# Contactor_Switching.net
KiCad netlist of a schematic drawn in Altium Designer
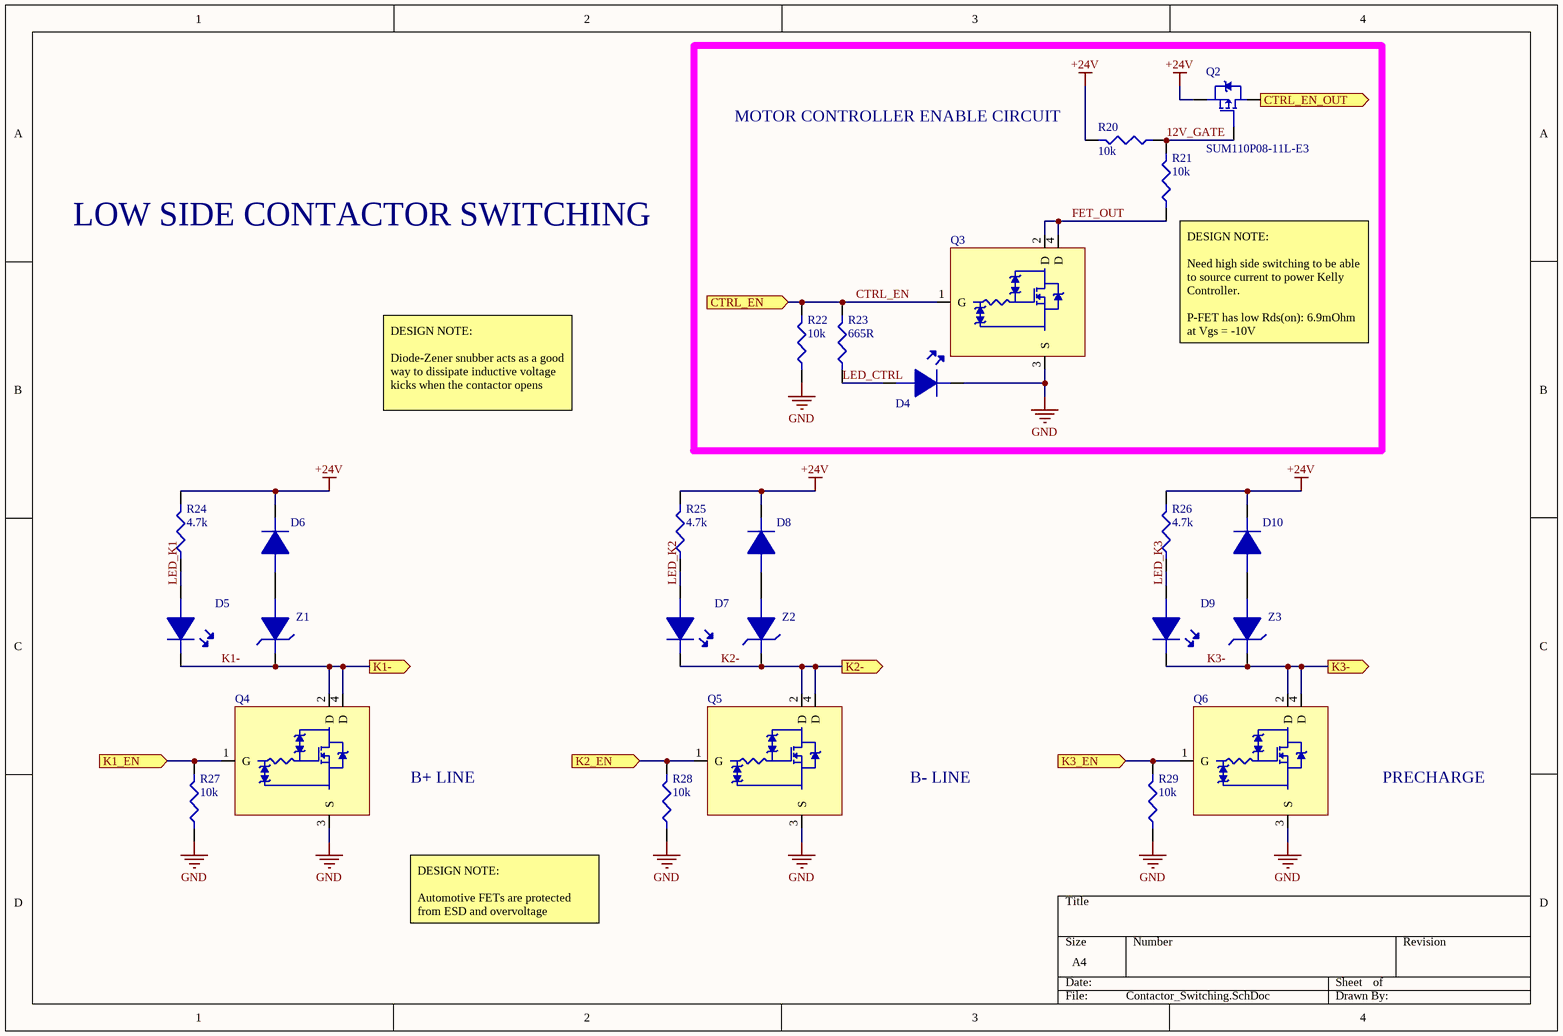
[diagram p0: Contactor_Switching.SchDoc]

(export (version "E")
  (design (tool "Eeschema 10.0.6"))
  (components
    (comp (ref "D4")
      (value "LTST-C191TBKT-5A")
      (footprint "LED_0603")
      (description "LED BLUE CLEAR 0603 SMD")
      (fields (field (name "MANUFACTURER") "Vishay Lite-On") (field (name "VOLTAGE") "29V"))
      (libsource (lib "PHANTOM_LIBRARY") (part "LTST-C191TBKT-5A"))
    )
    (comp (ref "D5")
      (value "LTST-C191TBKT-5A")
      (footprint "LED_0603")
      (description "LED BLUE CLEAR 0603 SMD")
      (fields (field (name "MANUFACTURER") "Vishay Lite-On") (field (name "VOLTAGE") "29V"))
      (libsource (lib "PHANTOM_LIBRARY") (part "LTST-C191TBKT-5A"))
    )
    (comp (ref "D6")
      (value "S3BB-TP")
      (footprint "DO-214AA_Diode")
      (description "DIODE GEN PURP 100V 3A DO214AA")
      (fields (field (name "MANUFACTURER") "MCC"))
      (libsource (lib "PHANTOM_LIBRARY") (part "S3BB-TP"))
    )
    (comp (ref "D7")
      (value "LTST-C191TBKT-5A")
      (footprint "LED_0603")
      (description "LED BLUE CLEAR 0603 SMD")
      (fields (field (name "MANUFACTURER") "Vishay Lite-On") (field (name "VOLTAGE") "29V"))
      (libsource (lib "PHANTOM_LIBRARY") (part "LTST-C191TBKT-5A"))
    )
    (comp (ref "D8")
      (value "S3BB-TP")
      (footprint "DO-214AA_Diode")
      (description "DIODE GEN PURP 100V 3A DO214AA")
      (fields (field (name "MANUFACTURER") "MCC"))
      (libsource (lib "PHANTOM_LIBRARY") (part "S3BB-TP"))
    )
    (comp (ref "D9")
      (value "LTST-C191TBKT-5A")
      (footprint "LED_0603")
      (description "LED BLUE CLEAR 0603 SMD")
      (fields (field (name "MANUFACTURER") "Vishay Lite-On") (field (name "VOLTAGE") "29V"))
      (libsource (lib "PHANTOM_LIBRARY") (part "LTST-C191TBKT-5A"))
    )
    (comp (ref "D10")
      (value "S3BB-TP")
      (footprint "DO-214AA_Diode")
      (description "DIODE GEN PURP 100V 3A DO214AA")
      (fields (field (name "MANUFACTURER") "MCC"))
      (libsource (lib "PHANTOM_LIBRARY") (part "S3BB-TP"))
    )
    (comp (ref "Q2")
      (value "SUM110P08-11L-E3")
      (footprint "D2PAK_FETs")
      (description "Trans MOSFET P-CH 80V 23.5A 3-Pin(2+Tab) TO-263")
      (fields (field (name "MANUFACTURER") "Vishay"))
      (libsource (lib "PHANTOM_LIBRARY") (part "SUM110P08-11L-E3"))
    )
    (comp (ref "Q3")
      (value "NCV8406ASTT1G")
      (footprint "SOT-223_NFET")
      (description "Self-Protected Low Side Driver Automotive 4-Pin(3+Tab) SOT-223 T/R")
      (fields (field (name "MANUFACTURER") "ON Semiconductor"))
      (libsource (lib "PHANTOM_LIBRARY") (part "NCV8406ASTT1G"))
    )
    (comp (ref "Q4")
      (value "NCV8406ASTT1G")
      (footprint "SOT-223_NFET")
      (description "Self-Protected Low Side Driver Automotive 4-Pin(3+Tab) SOT-223 T/R")
      (fields (field (name "MANUFACTURER") "ON Semiconductor"))
      (libsource (lib "PHANTOM_LIBRARY") (part "NCV8406ASTT1G"))
    )
    (comp (ref "Q5")
      (value "NCV8406ASTT1G")
      (footprint "SOT-223_NFET")
      (description "Self-Protected Low Side Driver Automotive 4-Pin(3+Tab) SOT-223 T/R")
      (fields (field (name "MANUFACTURER") "ON Semiconductor"))
      (libsource (lib "PHANTOM_LIBRARY") (part "NCV8406ASTT1G"))
    )
    (comp (ref "Q6")
      (value "NCV8406ASTT1G")
      (footprint "SOT-223_NFET")
      (description "Self-Protected Low Side Driver Automotive 4-Pin(3+Tab) SOT-223 T/R")
      (fields (field (name "MANUFACTURER") "ON Semiconductor"))
      (libsource (lib "PHANTOM_LIBRARY") (part "NCV8406ASTT1G"))
    )
    (comp (ref "R20")
      (value "10k")
      (footprint "R0805")
      (description "RES SMD 10K OHM 1% 1/8W 0805")
      (fields
        (field (name "MANUFACTURER") "Yageo Phycomp")
        (field (name "MANUFACTURER PART NUMBER") "RC0805FR-071KL")
      )
      (libsource (lib "PHANTOM_LIBRARY") (part "RC0805FR-071KL"))
    )
    (comp (ref "R21")
      (value "10k")
      (footprint "R0805")
      (description "RES SMD 10K OHM 1% 1/8W 0805")
      (fields
        (field (name "MANUFACTURER") "Yageo Phycomp")
        (field (name "MANUFACTURER PART NUMBER") "RC0805FR-071KL")
      )
      (libsource (lib "PHANTOM_LIBRARY") (part "RC0805FR-071KL"))
    )
    (comp (ref "R22")
      (value "10k")
      (footprint "R0805")
      (description "RES SMD 10K OHM 1% 1/8W 0805")
      (fields
        (field (name "MANUFACTURER") "Yageo Phycomp")
        (field (name "MANUFACTURER PART NUMBER") "RC0805FR-071KL")
      )
      (libsource (lib "PHANTOM_LIBRARY") (part "RC0805FR-071KL"))
    )
    (comp (ref "R23")
      (value "665R")
      (footprint "R0805")
      (description "RES SMD 665 OHM 1% 1/8W 0805")
      (fields
        (field (name "MANUFACTURER") "Yageo")
        (field (name "MANUFACTURER PART NUMBER") "RC0805FR-07665RL")
      )
      (libsource (lib "PHANTOM_LIBRARY") (part "RC0805FR-07665RL"))
    )
    (comp (ref "R24")
      (value "4.7k")
      (footprint "R0805")
      (description "RES SMD 4.7K OHM 1% 1/8W 0805")
      (fields
        (field (name "MANUFACTURER") "Yageo")
        (field (name "MANUFACTURER PART NUMBER") "RC0805FR-074K7L")
      )
      (libsource (lib "PHANTOM_LIBRARY") (part "RC0805FR-074K7L"))
    )
    (comp (ref "R25")
      (value "4.7k")
      (footprint "R0805")
      (description "RES SMD 4.7K OHM 1% 1/8W 0805")
      (fields
        (field (name "MANUFACTURER") "Yageo")
        (field (name "MANUFACTURER PART NUMBER") "RC0805FR-074K7L")
      )
      (libsource (lib "PHANTOM_LIBRARY") (part "RC0805FR-074K7L"))
    )
    (comp (ref "R26")
      (value "4.7k")
      (footprint "R0805")
      (description "RES SMD 4.7K OHM 1% 1/8W 0805")
      (fields
        (field (name "MANUFACTURER") "Yageo")
        (field (name "MANUFACTURER PART NUMBER") "RC0805FR-074K7L")
      )
      (libsource (lib "PHANTOM_LIBRARY") (part "RC0805FR-074K7L"))
    )
    (comp (ref "R27")
      (value "10k")
      (footprint "R0805")
      (description "RES SMD 10K OHM 1% 1/8W 0805")
      (fields
        (field (name "MANUFACTURER") "Yageo Phycomp")
        (field (name "MANUFACTURER PART NUMBER") "RC0805FR-071KL")
      )
      (libsource (lib "PHANTOM_LIBRARY") (part "RC0805FR-071KL"))
    )
    (comp (ref "R28")
      (value "10k")
      (footprint "R0805")
      (description "RES SMD 10K OHM 1% 1/8W 0805")
      (fields
        (field (name "MANUFACTURER") "Yageo Phycomp")
        (field (name "MANUFACTURER PART NUMBER") "RC0805FR-071KL")
      )
      (libsource (lib "PHANTOM_LIBRARY") (part "RC0805FR-071KL"))
    )
    (comp (ref "R29")
      (value "10k")
      (footprint "R0805")
      (description "RES SMD 10K OHM 1% 1/8W 0805")
      (fields
        (field (name "MANUFACTURER") "Yageo Phycomp")
        (field (name "MANUFACTURER PART NUMBER") "RC0805FR-071KL")
      )
      (libsource (lib "PHANTOM_LIBRARY") (part "RC0805FR-071KL"))
    )
    (comp (ref "Z1")
      (value "12V")
      (footprint "DO-214AA_Diode")
      (description "DIODE ZENER 12V 5W DO214AA")
      (fields (field (name "MANUFACTURER") "MCC") (field (name "MANUFACTURER PART NUMBER") "SMBJ5349B-TP"))
      (libsource (lib "PHANTOM_LIBRARY") (part "SMBJ5349B-TP"))
    )
    (comp (ref "Z2")
      (value "12V")
      (footprint "DO-214AA_Diode")
      (description "DIODE ZENER 12V 5W DO214AA")
      (fields (field (name "MANUFACTURER") "MCC") (field (name "MANUFACTURER PART NUMBER") "SMBJ5349B-TP"))
      (libsource (lib "PHANTOM_LIBRARY") (part "SMBJ5349B-TP"))
    )
    (comp (ref "Z3")
      (value "12V")
      (footprint "DO-214AA_Diode")
      (description "DIODE ZENER 12V 5W DO214AA")
      (fields (field (name "MANUFACTURER") "MCC") (field (name "MANUFACTURER PART NUMBER") "SMBJ5349B-TP"))
      (libsource (lib "PHANTOM_LIBRARY") (part "SMBJ5349B-TP"))
    )
  )
  (nets
    (net (code "1") (name "+24V") (class "Default")
      (node (ref "D10") (pin "2") (pinfunction "2_2") (pintype "passive"))
      (node (ref "D6") (pin "2") (pinfunction "2_2") (pintype "passive"))
      (node (ref "D8") (pin "2") (pinfunction "2_2") (pintype "passive"))
      (node (ref "Q2") (pin "4") (pinfunction "4_4") (pintype "passive"))
      (node (ref "R20") (pin "2") (pinfunction "2_2") (pintype "passive"))
      (node (ref "R24") (pin "2") (pinfunction "2_2") (pintype "passive"))
      (node (ref "R25") (pin "2") (pinfunction "2_2") (pintype "passive"))
      (node (ref "R26") (pin "2") (pinfunction "2_2") (pintype "passive"))
    )
    (net (code "2") (name "/12V_GATE") (class "Default")
      (node (ref "Q2") (pin "1") (pinfunction "1_1") (pintype "passive"))
      (node (ref "R20") (pin "1") (pinfunction "1_1") (pintype "passive"))
      (node (ref "R21") (pin "2") (pinfunction "2_2") (pintype "passive"))
    )
    (net (code "3") (name "/CTRL_EN") (class "Default")
      (node (ref "Q3") (pin "1") (pinfunction "G_1") (pintype "passive"))
      (node (ref "R22") (pin "2") (pinfunction "2_2") (pintype "passive"))
      (node (ref "R23") (pin "2") (pinfunction "2_2") (pintype "passive"))
    )
    (net (code "4") (name "/CTRL_EN_OUT") (class "Default")
      (node (ref "Q2") (pin "3") (pinfunction "3_3") (pintype "passive"))
    )
    (net (code "5") (name "/FET_OUT") (class "Default")
      (node (ref "Q3") (pin "2") (pinfunction "D_2") (pintype "passive"))
      (node (ref "Q3") (pin "4") (pinfunction "D_4") (pintype "passive"))
      (node (ref "R21") (pin "1") (pinfunction "1_1") (pintype "passive"))
    )
    (net (code "6") (name "/K1-") (class "Default")
      (node (ref "D5") (pin "2") (pinfunction "2_2") (pintype "passive"))
      (node (ref "Q4") (pin "2") (pinfunction "D_2") (pintype "passive"))
      (node (ref "Q4") (pin "4") (pinfunction "D_4") (pintype "passive"))
      (node (ref "Z1") (pin "2") (pinfunction "2_2") (pintype "passive"))
    )
    (net (code "7") (name "/K1_EN") (class "Default")
      (node (ref "Q4") (pin "1") (pinfunction "G_1") (pintype "passive"))
      (node (ref "R27") (pin "2") (pinfunction "2_2") (pintype "passive"))
    )
    (net (code "8") (name "/K2-") (class "Default")
      (node (ref "D7") (pin "2") (pinfunction "2_2") (pintype "passive"))
      (node (ref "Q5") (pin "2") (pinfunction "D_2") (pintype "passive"))
      (node (ref "Q5") (pin "4") (pinfunction "D_4") (pintype "passive"))
      (node (ref "Z2") (pin "2") (pinfunction "2_2") (pintype "passive"))
    )
    (net (code "9") (name "/K2_EN") (class "Default")
      (node (ref "Q5") (pin "1") (pinfunction "G_1") (pintype "passive"))
      (node (ref "R28") (pin "2") (pinfunction "2_2") (pintype "passive"))
    )
    (net (code "10") (name "/K3-") (class "Default")
      (node (ref "D9") (pin "2") (pinfunction "2_2") (pintype "passive"))
      (node (ref "Q6") (pin "2") (pinfunction "D_2") (pintype "passive"))
      (node (ref "Q6") (pin "4") (pinfunction "D_4") (pintype "passive"))
      (node (ref "Z3") (pin "2") (pinfunction "2_2") (pintype "passive"))
    )
    (net (code "11") (name "/K3_EN") (class "Default")
      (node (ref "Q6") (pin "1") (pinfunction "G_1") (pintype "passive"))
      (node (ref "R29") (pin "2") (pinfunction "2_2") (pintype "passive"))
    )
    (net (code "12") (name "/LED_CTRL") (class "Default")
      (node (ref "D4") (pin "1") (pinfunction "1_1") (pintype "passive"))
      (node (ref "R23") (pin "1") (pinfunction "1_1") (pintype "passive"))
    )
    (net (code "13") (name "/LED_K1") (class "Default")
      (node (ref "D5") (pin "1") (pinfunction "1_1") (pintype "passive"))
      (node (ref "R24") (pin "1") (pinfunction "1_1") (pintype "passive"))
    )
    (net (code "14") (name "/LED_K2") (class "Default")
      (node (ref "D7") (pin "1") (pinfunction "1_1") (pintype "passive"))
      (node (ref "R25") (pin "1") (pinfunction "1_1") (pintype "passive"))
    )
    (net (code "15") (name "/LED_K3") (class "Default")
      (node (ref "D9") (pin "1") (pinfunction "1_1") (pintype "passive"))
      (node (ref "R26") (pin "1") (pinfunction "1_1") (pintype "passive"))
    )
    (net (code "16") (name "GND") (class "Default")
      (node (ref "D4") (pin "2") (pinfunction "2_2") (pintype "passive"))
      (node (ref "Q3") (pin "3") (pinfunction "S_3") (pintype "passive"))
      (node (ref "Q4") (pin "3") (pinfunction "S_3") (pintype "passive"))
      (node (ref "Q5") (pin "3") (pinfunction "S_3") (pintype "passive"))
      (node (ref "Q6") (pin "3") (pinfunction "S_3") (pintype "passive"))
      (node (ref "R22") (pin "1") (pinfunction "1_1") (pintype "passive"))
      (node (ref "R27") (pin "1") (pinfunction "1_1") (pintype "passive"))
      (node (ref "R28") (pin "1") (pinfunction "1_1") (pintype "passive"))
      (node (ref "R29") (pin "1") (pinfunction "1_1") (pintype "passive"))
    )
    (net (code "17") (name "Net-(D6-Pad1)") (class "Default")
      (node (ref "D6") (pin "1") (pinfunction "1_1") (pintype "passive"))
      (node (ref "Z1") (pin "1") (pinfunction "1_1") (pintype "passive"))
    )
    (net (code "18") (name "Net-(D8-Pad1)") (class "Default")
      (node (ref "D8") (pin "1") (pinfunction "1_1") (pintype "passive"))
      (node (ref "Z2") (pin "1") (pinfunction "1_1") (pintype "passive"))
    )
    (net (code "19") (name "Net-(D10-Pad1)") (class "Default")
      (node (ref "D10") (pin "1") (pinfunction "1_1") (pintype "passive"))
      (node (ref "Z3") (pin "1") (pinfunction "1_1") (pintype "passive"))
    )
  )
)
